# Rx_power.net
KiCad netlist of a schematic drawn in Altium Designer
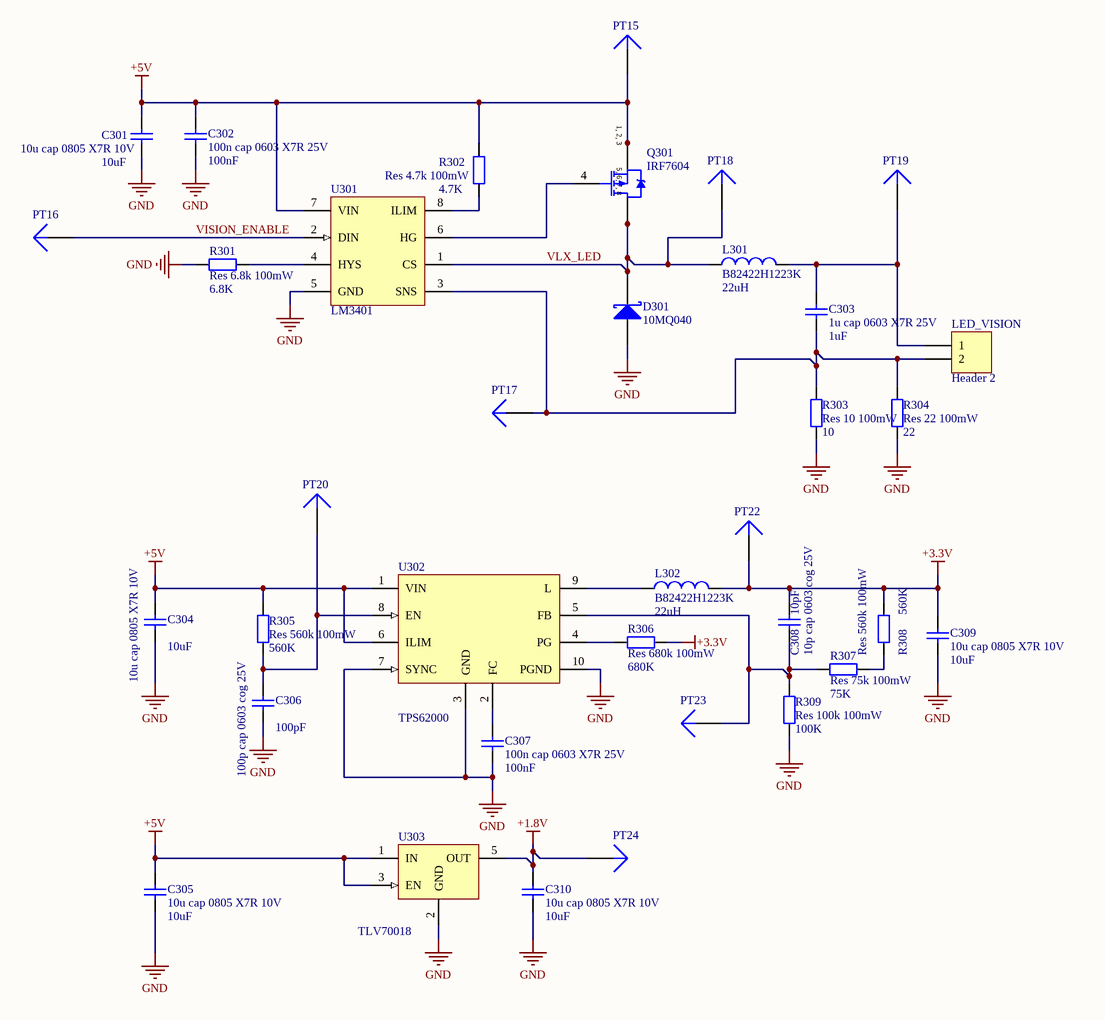
[diagram p0: Rx_power.SchDoc]

(export (version "E")
  (design (tool "Eeschema 10.0.6"))
  (components
    (comp (ref "C301")
      (value "10u cap 0805 X7R 10V")
      (footprint "0805")
      (description "Capacitor")
      (fields (field (name "ALTIUM_VALUE") "10uF") (field (name "PUBLISHER") "Altium Limited"))
      (libsource (lib "Miscellaneous Devices") (part "Cap"))
    )
    (comp (ref "C302")
      (value "100n cap 0603 X7R 25V")
      (footprint "0603")
      (description "Capacitor")
      (fields (field (name "ALTIUM_VALUE") "100nF") (field (name "PUBLISHER") "Altium Limited"))
      (libsource (lib "Miscellaneous Devices") (part "Cap"))
    )
    (comp (ref "C303")
      (value "1u cap 0603 X7R 25V")
      (footprint "0603")
      (description "Capacitor")
      (fields (field (name "ALTIUM_VALUE") "1uF") (field (name "PUBLISHER") "Altium Limited"))
      (libsource (lib "Miscellaneous Devices") (part "Cap"))
    )
    (comp (ref "C304")
      (value "10u cap 0805 X7R 10V")
      (footprint "0805")
      (description "Capacitor")
      (fields (field (name "ALTIUM_VALUE") "10uF") (field (name "PUBLISHER") "Altium Limited"))
      (libsource (lib "Miscellaneous Devices") (part "Cap"))
    )
    (comp (ref "C305")
      (value "10u cap 0805 X7R 10V")
      (footprint "0805")
      (description "Capacitor")
      (fields (field (name "ALTIUM_VALUE") "10uF") (field (name "PUBLISHER") "Altium Limited"))
      (libsource (lib "Miscellaneous Devices") (part "Cap"))
    )
    (comp (ref "C306")
      (value "100p cap 0603 cog 25V")
      (footprint "0603")
      (description "Capacitor")
      (fields (field (name "ALTIUM_VALUE") "100pF") (field (name "PUBLISHER") "Altium Limited"))
      (libsource (lib "Miscellaneous Devices") (part "Cap"))
    )
    (comp (ref "C307")
      (value "100n cap 0603 X7R 25V")
      (footprint "0603")
      (description "Capacitor")
      (fields (field (name "ALTIUM_VALUE") "100nF") (field (name "PUBLISHER") "Altium Limited"))
      (libsource (lib "Miscellaneous Devices") (part "Cap"))
    )
    (comp (ref "C308")
      (value "10p cap 0603 cog 25V")
      (footprint "0603")
      (description "Capacitor")
      (fields (field (name "ALTIUM_VALUE") "10pF") (field (name "PUBLISHER") "Altium Limited"))
      (libsource (lib "Miscellaneous Devices") (part "Cap"))
    )
    (comp (ref "C309")
      (value "10u cap 0805 X7R 10V")
      (footprint "0805")
      (description "Capacitor")
      (fields (field (name "ALTIUM_VALUE") "10uF") (field (name "PUBLISHER") "Altium Limited"))
      (libsource (lib "Miscellaneous Devices") (part "Cap"))
    )
    (comp (ref "C310")
      (value "10u cap 0805 X7R 10V")
      (footprint "0805")
      (description "Capacitor")
      (fields (field (name "ALTIUM_VALUE") "10uF") (field (name "PUBLISHER") "Altium Limited"))
      (libsource (lib "Miscellaneous Devices") (part "Cap"))
    )
    (comp (ref "D301")
      (value "10MQ040")
      (footprint "D-64")
      (description "Schottky Rectifier")
      (fields (field (name "PUBLISHER") "Altium Limited"))
      (libsource (lib "IR Rectifier - Schottky") (part "10MQ040"))
    )
    (comp (ref "L301")
      (value "B82422H1223K")
      (footprint "1210")
      (description "Inductor")
      (fields (field (name "ALTIUM_VALUE") "22uH") (field (name "PUBLISHER") "Altium Limited"))
      (libsource (lib "Miscellaneous Devices") (part "Inductor"))
    )
    (comp (ref "L302")
      (value "B82422H1223K")
      (footprint "1210")
      (description "Inductor")
      (fields (field (name "ALTIUM_VALUE") "22uH") (field (name "PUBLISHER") "Altium Limited"))
      (libsource (lib "Miscellaneous Devices") (part "Inductor"))
    )
    (comp (ref "LED_VISION")
      (value "Header 2")
      (footprint "HDR1X2")
      (description "Header, 2-Pin")
      (fields (field (name "PUBLISHER") "Altium Limited"))
      (libsource (lib "Miscellaneous Connectors") (part "Header 2"))
    )
    (comp (ref "PT15")
      (value "Plug")
      (footprint "TP")
      (fields (field (name "PUBLISHER") "Altium Limited"))
      (libsource (lib "Miscellaneous Connectors") (part "Plug"))
    )
    (comp (ref "PT16")
      (value "Plug")
      (footprint "TP")
      (fields (field (name "PUBLISHER") "Altium Limited"))
      (libsource (lib "Miscellaneous Connectors") (part "Plug"))
    )
    (comp (ref "PT17")
      (value "Plug")
      (footprint "TP")
      (fields (field (name "PUBLISHER") "Altium Limited"))
      (libsource (lib "Miscellaneous Connectors") (part "Plug"))
    )
    (comp (ref "PT18")
      (value "Plug")
      (footprint "TP")
      (fields (field (name "PUBLISHER") "Altium Limited"))
      (libsource (lib "Miscellaneous Connectors") (part "Plug"))
    )
    (comp (ref "PT19")
      (value "Plug")
      (footprint "TP")
      (fields (field (name "PUBLISHER") "Altium Limited"))
      (libsource (lib "Miscellaneous Connectors") (part "Plug"))
    )
    (comp (ref "PT20")
      (value "Plug")
      (footprint "TP")
      (fields (field (name "PUBLISHER") "Altium Limited"))
      (libsource (lib "Miscellaneous Connectors") (part "Plug"))
    )
    (comp (ref "PT22")
      (value "Plug")
      (footprint "TP")
      (fields (field (name "PUBLISHER") "Altium Limited"))
      (libsource (lib "Miscellaneous Connectors") (part "Plug"))
    )
    (comp (ref "PT23")
      (value "Plug")
      (footprint "TP")
      (fields (field (name "PUBLISHER") "Altium Limited"))
      (libsource (lib "Miscellaneous Connectors") (part "Plug"))
    )
    (comp (ref "PT24")
      (value "Plug")
      (footprint "TP")
      (fields (field (name "PUBLISHER") "Altium Limited"))
      (libsource (lib "Miscellaneous Connectors") (part "Plug"))
    )
    (comp (ref "Q301")
      (value "IRF7604")
      (footprint "Micro8")
      (description "HEXFET Power MOSFET")
      (fields (field (name "PUBLISHER") "Altium Limited"))
      (libsource (lib "IR Discrete MOSFET - Power") (part "IRF7604"))
    )
    (comp (ref "R301")
      (value "Res 6.8k 100mW")
      (footprint "0603")
      (description "Resistor")
      (fields (field (name "ALTIUM_VALUE") "6.8K") (field (name "PUBLISHER") "Altium Limited"))
      (libsource (lib "") (part "Res2_1"))
    )
    (comp (ref "R302")
      (value "Res 4.7k 100mW")
      (footprint "0603")
      (description "Resistor")
      (fields (field (name "ALTIUM_VALUE") "4.7K") (field (name "PUBLISHER") "Altium Limited"))
      (libsource (lib "Miscellaneous Devices") (part "Res2"))
    )
    (comp (ref "R303")
      (value "Res 10 100mW")
      (footprint "0603")
      (description "Resistor")
      (fields (field (name "ALTIUM_VALUE") "10") (field (name "PUBLISHER") "Altium Limited"))
      (libsource (lib "Miscellaneous Devices") (part "Res2"))
    )
    (comp (ref "R304")
      (value "Res 22 100mW")
      (footprint "0603")
      (description "Resistor")
      (fields (field (name "ALTIUM_VALUE") "22") (field (name "PUBLISHER") "Altium Limited"))
      (libsource (lib "Miscellaneous Devices") (part "Res2"))
    )
    (comp (ref "R305")
      (value "Res 560k 100mW")
      (footprint "0603")
      (description "Resistor")
      (fields (field (name "ALTIUM_VALUE") "560K") (field (name "PUBLISHER") "Altium Limited"))
      (libsource (lib "Miscellaneous Devices") (part "Res2"))
    )
    (comp (ref "R306")
      (value "Res 680k 100mW")
      (footprint "0603")
      (description "Resistor")
      (fields (field (name "ALTIUM_VALUE") "680K") (field (name "PUBLISHER") "Altium Limited"))
      (libsource (lib "") (part "Res2_1"))
    )
    (comp (ref "R307")
      (value "Res 75k 100mW")
      (footprint "0603")
      (description "Resistor")
      (fields (field (name "ALTIUM_VALUE") "75K") (field (name "PUBLISHER") "Altium Limited"))
      (libsource (lib "") (part "Res2_1"))
    )
    (comp (ref "R308")
      (value "Res 560k 100mW")
      (footprint "0603")
      (description "Resistor")
      (fields (field (name "ALTIUM_VALUE") "560K") (field (name "PUBLISHER") "Altium Limited"))
      (libsource (lib "Miscellaneous Devices") (part "Res2"))
    )
    (comp (ref "R309")
      (value "Res 100k 100mW")
      (footprint "0603")
      (description "Resistor")
      (fields (field (name "ALTIUM_VALUE") "100K") (field (name "PUBLISHER") "Altium Limited"))
      (libsource (lib "Miscellaneous Devices") (part "Res2"))
    )
    (comp (ref "U301")
      (value "LM3401")
      (footprint "MSOP8")
      (description "Hysteretic PFET Controller for High Power LED Drive")
      (libsource (lib "Oufff_Lib2") (part "LM3401"))
    )
    (comp (ref "U302")
      (value "TPS62000")
      (footprint "MS10")
      (description "HIGH-EFFICIENCY STEP-DOWN LOW POWER DC-DC CONVERTER")
      (libsource (lib "Oufff_Lib2") (part "TPS6200x"))
    )
    (comp (ref "U303")
      (value "TLV70018")
      (footprint "SOT23-5")
      (description "200-mA, Low-IQ, Low-Dropout Regulator for Portable Devices")
      (libsource (lib "Oufff_Lib2") (part "TLV700xx"))
    )
  )
  (nets
    (net (code "1") (name "+1.8V") (class "Default")
      (node (ref "C310") (pin "2") (pinfunction "2_2") (pintype "passive"))
      (node (ref "PT24") (pin "1") (pinfunction "1_1") (pintype "passive"))
      (node (ref "U303") (pin "5") (pinfunction "OUT_5") (pintype "power_in"))
    )
    (net (code "2") (name "+3.3V") (class "Default")
      (node (ref "C308") (pin "2") (pinfunction "2_2") (pintype "passive"))
      (node (ref "C309") (pin "2") (pinfunction "2_2") (pintype "passive"))
      (node (ref "L302") (pin "2") (pinfunction "2_2") (pintype "passive"))
      (node (ref "PT22") (pin "1") (pinfunction "1_1") (pintype "passive"))
      (node (ref "R306") (pin "2") (pinfunction "2_2") (pintype "passive"))
      (node (ref "R308") (pin "2") (pinfunction "2_2") (pintype "passive"))
    )
    (net (code "3") (name "+5V") (class "Default")
      (node (ref "C301") (pin "2") (pinfunction "2_2") (pintype "passive"))
      (node (ref "C302") (pin "2") (pinfunction "2_2") (pintype "passive"))
      (node (ref "C304") (pin "2") (pinfunction "2_2") (pintype "passive"))
      (node (ref "C305") (pin "2") (pinfunction "2_2") (pintype "passive"))
      (node (ref "PT15") (pin "1") (pinfunction "1_1") (pintype "passive"))
      (node (ref "Q301") (pin "1") (pinfunction "S_1") (pintype "passive"))
      (node (ref "Q301") (pin "2") (pinfunction "S_2") (pintype "passive"))
      (node (ref "Q301") (pin "3") (pinfunction "S_3") (pintype "passive"))
      (node (ref "R302") (pin "2") (pinfunction "2_2") (pintype "passive"))
      (node (ref "R305") (pin "2") (pinfunction "2_2") (pintype "passive"))
      (node (ref "U301") (pin "7") (pinfunction "VIN_7") (pintype "power_in"))
      (node (ref "U302") (pin "1") (pinfunction "VIN_1") (pintype "power_in"))
      (node (ref "U302") (pin "6") (pinfunction "ILIM_6") (pintype "passive"))
      (node (ref "U303") (pin "1") (pinfunction "IN_1") (pintype "power_in"))
      (node (ref "U303") (pin "3") (pinfunction "EN_3") (pintype "input"))
    )
    (net (code "4") (name "/VISION_ENABLE") (class "Default")
      (node (ref "PT16") (pin "1") (pinfunction "1_1") (pintype "passive"))
      (node (ref "U301") (pin "2") (pinfunction "DIN_2") (pintype "input"))
    )
    (net (code "5") (name "/VLX_LED") (class "Default")
      (node (ref "D301") (pin "2") (pinfunction "K_2") (pintype "passive"))
      (node (ref "L301") (pin "1") (pinfunction "1_1") (pintype "passive"))
      (node (ref "PT18") (pin "1") (pinfunction "1_1") (pintype "passive"))
      (node (ref "Q301") (pin "5") (pinfunction "D_5") (pintype "passive"))
      (node (ref "Q301") (pin "6") (pinfunction "D_6") (pintype "passive"))
      (node (ref "Q301") (pin "7") (pinfunction "D_7") (pintype "passive"))
      (node (ref "Q301") (pin "8") (pinfunction "D_8") (pintype "passive"))
      (node (ref "U301") (pin "1") (pinfunction "CS_1") (pintype "passive"))
    )
    (net (code "6") (name "GND") (class "Default")
      (node (ref "C301") (pin "1") (pinfunction "1_1") (pintype "passive"))
      (node (ref "C302") (pin "1") (pinfunction "1_1") (pintype "passive"))
      (node (ref "C304") (pin "1") (pinfunction "1_1") (pintype "passive"))
      (node (ref "C305") (pin "1") (pinfunction "1_1") (pintype "passive"))
      (node (ref "C306") (pin "1") (pinfunction "1_1") (pintype "passive"))
      (node (ref "C307") (pin "1") (pinfunction "1_1") (pintype "passive"))
      (node (ref "C309") (pin "1") (pinfunction "1_1") (pintype "passive"))
      (node (ref "C310") (pin "1") (pinfunction "1_1") (pintype "passive"))
      (node (ref "D301") (pin "1") (pinfunction "A_1") (pintype "passive"))
      (node (ref "R301") (pin "1") (pinfunction "1_1") (pintype "passive"))
      (node (ref "R303") (pin "1") (pinfunction "1_1") (pintype "passive"))
      (node (ref "R304") (pin "1") (pinfunction "1_1") (pintype "passive"))
      (node (ref "R309") (pin "1") (pinfunction "1_1") (pintype "passive"))
      (node (ref "U301") (pin "5") (pinfunction "GND_5") (pintype "power_in"))
      (node (ref "U302") (pin "10") (pinfunction "PGND_10") (pintype "power_in"))
      (node (ref "U302") (pin "3") (pinfunction "GND_3") (pintype "power_in"))
      (node (ref "U302") (pin "7") (pinfunction "SYNC_7") (pintype "input"))
      (node (ref "U303") (pin "2") (pinfunction "GND_2") (pintype "power_in"))
    )
    (net (code "7") (name "Net-(C303-Pad2)") (class "Default")
      (node (ref "C303") (pin "2") (pinfunction "2_2") (pintype "passive"))
      (node (ref "L301") (pin "2") (pinfunction "2_2") (pintype "passive"))
      (node (ref "LED_VISION") (pin "1") (pinfunction "1_1") (pintype "passive"))
      (node (ref "PT19") (pin "1") (pinfunction "1_1") (pintype "passive"))
    )
    (net (code "8") (name "Net-(Q301-G)") (class "Default")
      (node (ref "Q301") (pin "4") (pinfunction "G_4") (pintype "passive"))
      (node (ref "U301") (pin "6") (pinfunction "HG_6") (pintype "passive"))
    )
    (net (code "9") (name "Net-(R307-Pad2)") (class "Default")
      (node (ref "R307") (pin "2") (pinfunction "2_2") (pintype "passive"))
      (node (ref "R308") (pin "1") (pinfunction "1_1") (pintype "passive"))
    )
    (net (code "10") (name "Net-(U301-HYS)") (class "Default")
      (node (ref "R301") (pin "2") (pinfunction "2_2") (pintype "passive"))
      (node (ref "U301") (pin "4") (pinfunction "HYS_4") (pintype "passive"))
    )
    (net (code "11") (name "Net-(U301-ILIM)") (class "Default")
      (node (ref "R302") (pin "1") (pinfunction "1_1") (pintype "passive"))
      (node (ref "U301") (pin "8") (pinfunction "ILIM_8") (pintype "passive"))
    )
    (net (code "12") (name "Net-(U301-SNS)") (class "Default")
      (node (ref "C303") (pin "1") (pinfunction "1_1") (pintype "passive"))
      (node (ref "LED_VISION") (pin "2") (pinfunction "2_2") (pintype "passive"))
      (node (ref "PT17") (pin "1") (pinfunction "1_1") (pintype "passive"))
      (node (ref "R303") (pin "2") (pinfunction "2_2") (pintype "passive"))
      (node (ref "R304") (pin "2") (pinfunction "2_2") (pintype "passive"))
      (node (ref "U301") (pin "3") (pinfunction "SNS_3") (pintype "passive"))
    )
    (net (code "13") (name "Net-(U302-EN)") (class "Default")
      (node (ref "C306") (pin "2") (pinfunction "2_2") (pintype "passive"))
      (node (ref "PT20") (pin "1") (pinfunction "1_1") (pintype "passive"))
      (node (ref "R305") (pin "1") (pinfunction "1_1") (pintype "passive"))
      (node (ref "U302") (pin "8") (pinfunction "EN_8") (pintype "input"))
    )
    (net (code "14") (name "Net-(U302-FB)") (class "Default")
      (node (ref "C308") (pin "1") (pinfunction "1_1") (pintype "passive"))
      (node (ref "PT23") (pin "1") (pinfunction "1_1") (pintype "passive"))
      (node (ref "R307") (pin "1") (pinfunction "1_1") (pintype "passive"))
      (node (ref "R309") (pin "2") (pinfunction "2_2") (pintype "passive"))
      (node (ref "U302") (pin "5") (pinfunction "FB_5") (pintype "passive"))
    )
    (net (code "15") (name "Net-(U302-FC)") (class "Default")
      (node (ref "C307") (pin "2") (pinfunction "2_2") (pintype "passive"))
      (node (ref "U302") (pin "2") (pinfunction "FC_2") (pintype "passive"))
    )
    (net (code "16") (name "Net-(U302-L)") (class "Default")
      (node (ref "L302") (pin "1") (pinfunction "1_1") (pintype "passive"))
      (node (ref "U302") (pin "9") (pinfunction "L_9") (pintype "power_in"))
    )
    (net (code "17") (name "Net-(U302-PG)") (class "Default")
      (node (ref "R306") (pin "1") (pinfunction "1_1") (pintype "passive"))
      (node (ref "U302") (pin "4") (pinfunction "PG_4") (pintype "open_collector"))
    )
  )
)
